# stm32.net
KiCad netlist of a schematic drawn in Altium Designer
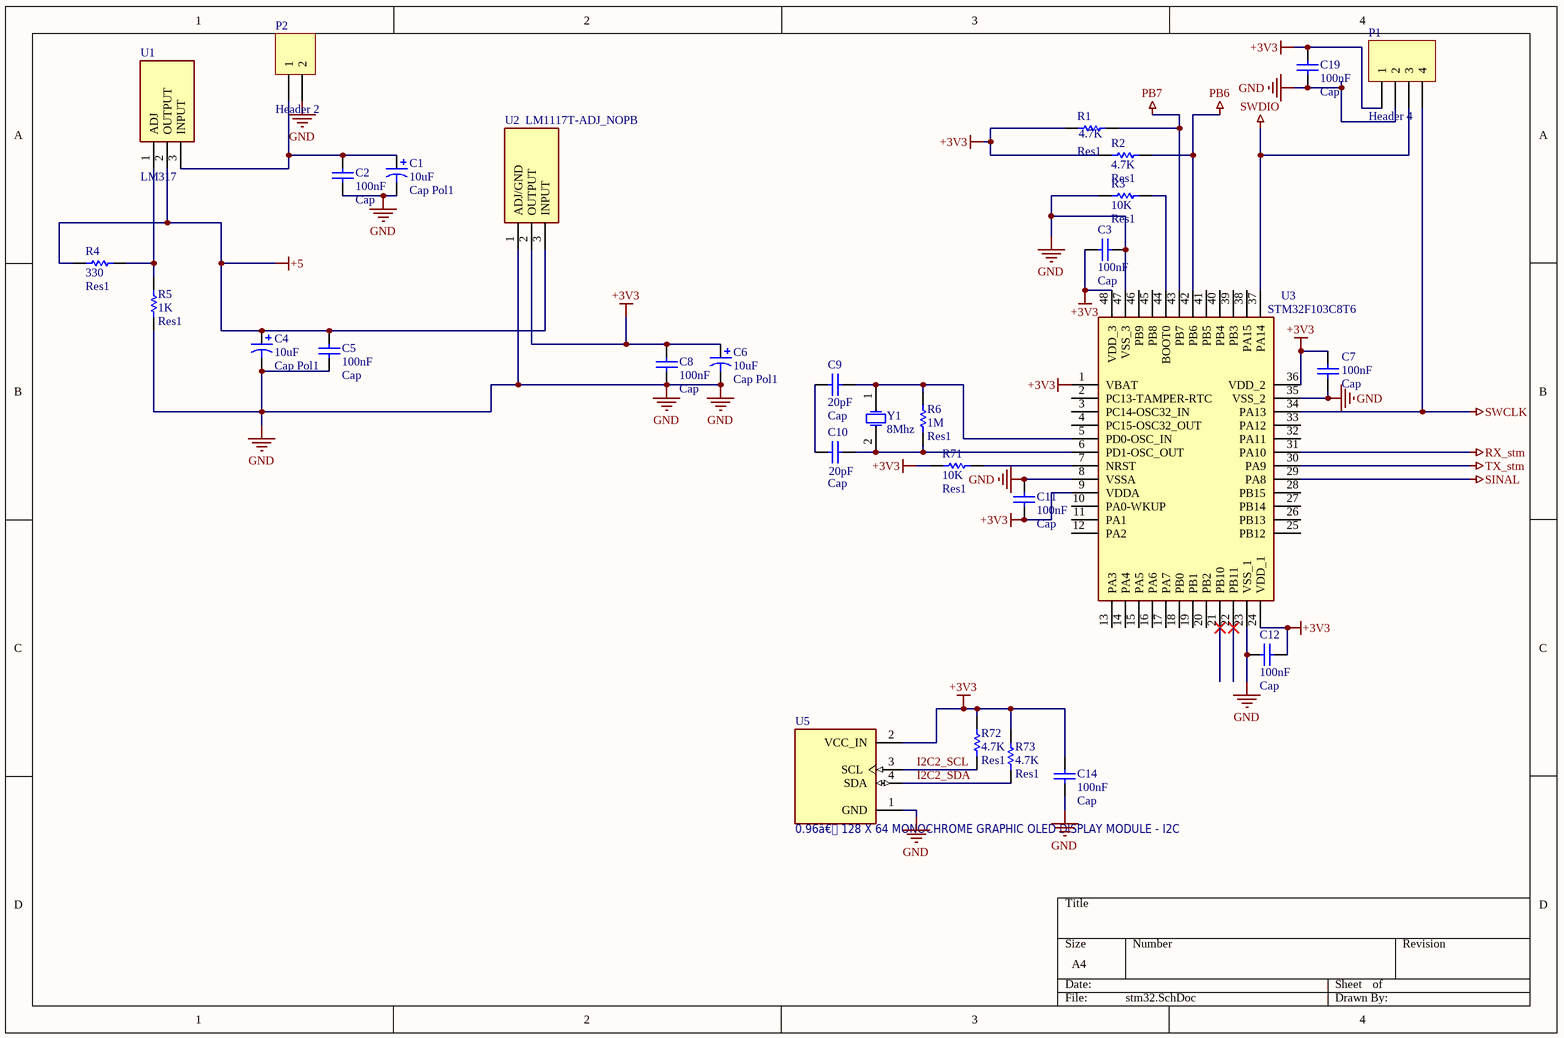
[diagram p0: stm32.SchDoc]

(export (version "E")
  (design (tool "Eeschema 10.0.6"))
  (components
    (comp (ref "C1")
      (value "Cap Pol1")
      (footprint "lib_footprint_projeto:CAP+10uF")
      (description "Polarized Capacitor (Radial)")
      (fields (field (name "ALTIUM_VALUE") "10uF") (field (name "PUBLISHER") "Altium Limited"))
      (libsource (lib "Miscellaneous Devices") (part "Cap Pol1"))
    )
    (comp (ref "C2")
      (value "Cap")
      (footprint "lib_footprint_projeto:CAP100N")
      (description "Capacitor")
      (fields (field (name "ALTIUM_VALUE") "100nF") (field (name "PUBLISHER") "Altium Limited"))
      (libsource (lib "Miscellaneous Devices") (part "Cap"))
    )
    (comp (ref "C3")
      (value "Cap")
      (footprint "lib_footprint_projeto:CAP100N")
      (description "Capacitor")
      (fields (field (name "ALTIUM_VALUE") "100nF") (field (name "PUBLISHER") "Altium Limited"))
      (libsource (lib "Miscellaneous Devices") (part "Cap"))
    )
    (comp (ref "C4")
      (value "Cap Pol1")
      (footprint "lib_footprint_projeto:CAP+10uF")
      (description "Polarized Capacitor (Radial)")
      (fields (field (name "ALTIUM_VALUE") "10uF") (field (name "PUBLISHER") "Altium Limited"))
      (libsource (lib "Miscellaneous Devices") (part "Cap Pol1"))
    )
    (comp (ref "C5")
      (value "Cap")
      (footprint "lib_footprint_projeto:CAP100N")
      (description "Capacitor")
      (fields (field (name "ALTIUM_VALUE") "100nF") (field (name "PUBLISHER") "Altium Limited"))
      (libsource (lib "Miscellaneous Devices") (part "Cap"))
    )
    (comp (ref "C6")
      (value "Cap Pol1")
      (footprint "lib_footprint_projeto:CAP+10uF")
      (description "Polarized Capacitor (Radial)")
      (fields (field (name "ALTIUM_VALUE") "10uF") (field (name "PUBLISHER") "Altium Limited"))
      (libsource (lib "Miscellaneous Devices") (part "Cap Pol1"))
    )
    (comp (ref "C7")
      (value "Cap")
      (footprint "lib_footprint_projeto:CAP100N")
      (description "Capacitor")
      (fields (field (name "ALTIUM_VALUE") "100nF") (field (name "PUBLISHER") "Altium Limited"))
      (libsource (lib "Miscellaneous Devices") (part "Cap"))
    )
    (comp (ref "C8")
      (value "Cap")
      (footprint "lib_footprint_projeto:CAP100N")
      (description "Capacitor")
      (fields (field (name "ALTIUM_VALUE") "100nF") (field (name "PUBLISHER") "Altium Limited"))
      (libsource (lib "Miscellaneous Devices") (part "Cap"))
    )
    (comp (ref "C9")
      (value "Cap")
      (footprint "lib_footprint_projeto:CAP20pF")
      (description "Capacitor")
      (fields (field (name "ALTIUM_VALUE") "20pF") (field (name "PUBLISHER") "Altium Limited"))
      (libsource (lib "Miscellaneous Devices") (part "Cap"))
    )
    (comp (ref "C10")
      (value "Cap")
      (footprint "lib_footprint_projeto:CAP20pF")
      (description "Capacitor")
      (fields (field (name "ALTIUM_VALUE") "20pF") (field (name "PUBLISHER") "Altium Limited"))
      (libsource (lib "Miscellaneous Devices") (part "Cap"))
    )
    (comp (ref "C11")
      (value "Cap")
      (footprint "lib_footprint_projeto:CAP100N")
      (description "Capacitor")
      (fields (field (name "ALTIUM_VALUE") "100nF") (field (name "PUBLISHER") "Altium Limited"))
      (libsource (lib "Miscellaneous Devices") (part "Cap"))
    )
    (comp (ref "C12")
      (value "Cap")
      (footprint "lib_footprint_projeto:CAP100N")
      (description "Capacitor")
      (fields (field (name "ALTIUM_VALUE") "100nF") (field (name "PUBLISHER") "Altium Limited"))
      (libsource (lib "Miscellaneous Devices") (part "Cap"))
    )
    (comp (ref "C14")
      (value "Cap")
      (footprint "lib_footprint_projeto:CAP100N")
      (description "Capacitor")
      (fields (field (name "ALTIUM_VALUE") "100nF") (field (name "PUBLISHER") "Altium Limited"))
      (libsource (lib "Miscellaneous Devices") (part "Cap"))
    )
    (comp (ref "C19")
      (value "Cap")
      (footprint "lib_footprint_projeto:CAP100N")
      (description "Capacitor")
      (fields (field (name "ALTIUM_VALUE") "100nF") (field (name "PUBLISHER") "Altium Limited"))
      (libsource (lib "Miscellaneous Devices") (part "Cap"))
    )
    (comp (ref "P1")
      (value "Header 4")
      (footprint "lib_footprint_projeto:Header 4, 90")
      (description "Header, 4-Pin")
      (fields (field (name "PUBLISHER") "Altium Limited"))
      (libsource (lib "Miscellaneous Connectors") (part "Header 4"))
    )
    (comp (ref "P2")
      (value "Header 2")
      (footprint "lib_footprint_projeto:Terminal block")
      (description "Header, 2-Pin")
      (fields (field (name "PUBLISHER") "Altium Limited"))
      (libsource (lib "Miscellaneous Connectors") (part "Header 2"))
    )
    (comp (ref "R1")
      (value "Res1")
      (footprint "lib_footprint_projeto:RES4.7K")
      (description "Resistor")
      (fields (field (name "ALTIUM_VALUE") "4.7K") (field (name "PUBLISHER") "Altium Limited"))
      (libsource (lib "Miscellaneous Devices") (part "Res1"))
    )
    (comp (ref "R2")
      (value "Res1")
      (footprint "lib_footprint_projeto:RES4.7K")
      (description "Resistor")
      (fields (field (name "ALTIUM_VALUE") "4.7K") (field (name "PUBLISHER") "Altium Limited"))
      (libsource (lib "Miscellaneous Devices") (part "Res1"))
    )
    (comp (ref "R3")
      (value "Res1")
      (footprint "lib_footprint_projeto:RES10K")
      (description "Resistor")
      (fields (field (name "ALTIUM_VALUE") "10K") (field (name "PUBLISHER") "Altium Limited"))
      (libsource (lib "Miscellaneous Devices") (part "Res1"))
    )
    (comp (ref "R4")
      (value "Res1")
      (footprint "lib_footprint_projeto:RES330")
      (description "Resistor")
      (fields (field (name "ALTIUM_VALUE") "330") (field (name "PUBLISHER") "Altium Limited"))
      (libsource (lib "Miscellaneous Devices") (part "Res1"))
    )
    (comp (ref "R5")
      (value "Res1")
      (footprint "lib_footprint_projeto:RES1K")
      (description "Resistor")
      (fields (field (name "ALTIUM_VALUE") "1K") (field (name "PUBLISHER") "Altium Limited"))
      (libsource (lib "Miscellaneous Devices") (part "Res1"))
    )
    (comp (ref "R6")
      (value "Res1")
      (footprint "lib_footprint_projeto:RES1M")
      (description "Resistor")
      (fields (field (name "ALTIUM_VALUE") "1M") (field (name "PUBLISHER") "Altium Limited"))
      (libsource (lib "Miscellaneous Devices") (part "Res1"))
    )
    (comp (ref "R71")
      (value "Res1")
      (footprint "lib_footprint_projeto:RES10K")
      (description "Resistor")
      (fields (field (name "ALTIUM_VALUE") "10K") (field (name "PUBLISHER") "Altium Limited"))
      (libsource (lib "Miscellaneous Devices") (part "Res1"))
    )
    (comp (ref "R72")
      (value "Res1")
      (footprint "lib_footprint_projeto:RES4.7K")
      (description "Resistor")
      (fields (field (name "ALTIUM_VALUE") "4.7K") (field (name "PUBLISHER") "Altium Limited"))
      (libsource (lib "Miscellaneous Devices") (part "Res1"))
    )
    (comp (ref "R73")
      (value "Res1")
      (footprint "lib_footprint_projeto:RES4.7K")
      (description "Resistor")
      (fields (field (name "ALTIUM_VALUE") "4.7K") (field (name "PUBLISHER") "Altium Limited"))
      (libsource (lib "Miscellaneous Devices") (part "Res1"))
    )
    (comp (ref "U1")
      (value "LM317")
      (footprint "LM317")
      (description "TO-220-3L Plastic-Encapsulate Voltage Regulators")
      (libsource (lib "LM317") (part "LM317"))
    )
    (comp (ref "U2")
      (value "LM1117T-ADJ_NOPB")
      (footprint "LM1117T-ADJ_NOPB")
      (description "Space saving 800-mA low-dropout linear regulator with internal current limit")
      (fields
        (field (name "MANUFACTURER_PART_NUMBER") "LM1117T-ADJ/NOPB")
        (field (name "MOUSER PART NUMBER") "926-LM1117T-ADJ/NOPB")
      )
      (libsource (lib "LM1117T-ADJ_NOPB") (part "LM1117T-ADJ_NOPB"))
    )
    (comp (ref "U3")
      (value "STM32F103C8T6")
      (footprint "STM32F103C8T6")
      (description "ARM Cortex-M3 STM32F1 Microcontroller IC 32-Bit Single-Core 72MHz 64KB (64K x 8) FLASH")
      (libsource (lib "STM32F103C8T6") (part "STM32F103C8T6"))
    )
    (comp (ref "U5")
      (value "0.96â€ 128 X 64 MONOCHROME GRAPHIC OLED DISPLAY MODULE - I2C")
      (footprint "lib_footprint_projeto:OLED")
      (fields (field (name "MF") "Display Module") (field (name "MP") "DM-OLED096-636"))
      (libsource (lib "DM-OLED096-636") (part "DM-OLED096-636"))
    )
    (comp (ref "Y1")
      (value "8Mhz")
      (footprint "lib_footprint_projeto:CRISTAL")
      (description "Crystal Oscillator 8Mhz XTAL Crystal, Thru-Hole; 2 Leads; Body 3.1 x 8.2 mm")
      (fields (field (name "PUBLISHER") "Altium Limited"))
      (libsource (lib "Miscellaneous Devices") (part "XTAL"))
    )
  )
  (nets
    (net (code "1") (name "+3V3") (class "Default")
      (node (ref "C11") (pin "1") (pinfunction "1_1") (pintype "passive"))
      (node (ref "C12") (pin "2") (pinfunction "2_2") (pintype "passive"))
      (node (ref "C14") (pin "2") (pinfunction "2_2") (pintype "passive"))
      (node (ref "C19") (pin "1") (pinfunction "1_1") (pintype "passive"))
      (node (ref "C3") (pin "1") (pinfunction "1_1") (pintype "passive"))
      (node (ref "C6") (pin "1") (pinfunction "1_1") (pintype "passive"))
      (node (ref "C7") (pin "2") (pinfunction "2_2") (pintype "passive"))
      (node (ref "C8") (pin "2") (pinfunction "2_2") (pintype "passive"))
      (node (ref "P1") (pin "1") (pinfunction "1_1") (pintype "passive"))
      (node (ref "R1") (pin "1") (pinfunction "1_1") (pintype "passive"))
      (node (ref "R2") (pin "1") (pinfunction "1_1") (pintype "passive"))
      (node (ref "R71") (pin "1") (pinfunction "1_1") (pintype "passive"))
      (node (ref "R72") (pin "2") (pinfunction "2_2") (pintype "passive"))
      (node (ref "R73") (pin "2") (pinfunction "2_2") (pintype "passive"))
      (node (ref "U2") (pin "2") (pinfunction "OUTPUT_2") (pintype "passive"))
      (node (ref "U3") (pin "1") (pinfunction "VBAT_1") (pintype "passive"))
      (node (ref "U3") (pin "24") (pinfunction "VDD_1_24") (pintype "passive"))
      (node (ref "U3") (pin "36") (pinfunction "VDD_2_36") (pintype "passive"))
      (node (ref "U3") (pin "48") (pinfunction "VDD_3_48") (pintype "passive"))
      (node (ref "U3") (pin "9") (pinfunction "VDDA_9") (pintype "passive"))
      (node (ref "U5") (pin "2") (pinfunction "VCC_IN_2") (pintype "power_in"))
    )
    (net (code "2") (name "+5") (class "Default")
      (node (ref "C4") (pin "1") (pinfunction "1_1") (pintype "passive"))
      (node (ref "C5") (pin "2") (pinfunction "2_2") (pintype "passive"))
      (node (ref "R4") (pin "1") (pinfunction "1_1") (pintype "passive"))
      (node (ref "U1") (pin "2") (pinfunction "OUTPUT_2") (pintype "passive"))
      (node (ref "U2") (pin "3") (pinfunction "INPUT_3") (pintype "passive"))
    )
    (net (code "3") (name "/I2C2_SCL") (class "Default")
      (node (ref "R72") (pin "1") (pinfunction "1_1") (pintype "passive"))
      (node (ref "U5") (pin "3") (pinfunction "SCL_3") (pintype "input"))
    )
    (net (code "4") (name "/I2C2_SDA") (class "Default")
      (node (ref "R73") (pin "1") (pinfunction "1_1") (pintype "passive"))
      (node (ref "U5") (pin "4") (pinfunction "SDA_4") (pintype "bidirectional"))
    )
    (net (code "5") (name "GND") (class "Default")
      (node (ref "C1") (pin "2") (pinfunction "2_2") (pintype "passive"))
      (node (ref "C11") (pin "2") (pinfunction "2_2") (pintype "passive"))
      (node (ref "C12") (pin "1") (pinfunction "1_1") (pintype "passive"))
      (node (ref "C14") (pin "1") (pinfunction "1_1") (pintype "passive"))
      (node (ref "C19") (pin "2") (pinfunction "2_2") (pintype "passive"))
      (node (ref "C2") (pin "1") (pinfunction "1_1") (pintype "passive"))
      (node (ref "C3") (pin "2") (pinfunction "2_2") (pintype "passive"))
      (node (ref "C4") (pin "2") (pinfunction "2_2") (pintype "passive"))
      (node (ref "C5") (pin "1") (pinfunction "1_1") (pintype "passive"))
      (node (ref "C6") (pin "2") (pinfunction "2_2") (pintype "passive"))
      (node (ref "C7") (pin "1") (pinfunction "1_1") (pintype "passive"))
      (node (ref "C8") (pin "1") (pinfunction "1_1") (pintype "passive"))
      (node (ref "P1") (pin "2") (pinfunction "2_2") (pintype "passive"))
      (node (ref "P2") (pin "2") (pinfunction "2_2") (pintype "passive"))
      (node (ref "R3") (pin "1") (pinfunction "1_1") (pintype "passive"))
      (node (ref "R5") (pin "1") (pinfunction "1_1") (pintype "passive"))
      (node (ref "U2") (pin "1") (pinfunction "ADJ/GND_1") (pintype "passive"))
      (node (ref "U3") (pin "23") (pinfunction "VSS_1_23") (pintype "passive"))
      (node (ref "U3") (pin "35") (pinfunction "VSS_2_35") (pintype "passive"))
      (node (ref "U3") (pin "47") (pinfunction "VSS_3_47") (pintype "passive"))
      (node (ref "U3") (pin "8") (pinfunction "VSSA_8") (pintype "passive"))
      (node (ref "U5") (pin "1") (pinfunction "GND_1") (pintype "power_in"))
    )
    (net (code "6") (name "Net-(C10-Pad1)") (class "Default")
      (node (ref "C10") (pin "1") (pinfunction "1_1") (pintype "passive"))
      (node (ref "C9") (pin "1") (pinfunction "1_1") (pintype "passive"))
    )
    (net (code "7") (name "Net-(U1-ADJ)") (class "Default")
      (node (ref "R4") (pin "2") (pinfunction "2_2") (pintype "passive"))
      (node (ref "R5") (pin "2") (pinfunction "2_2") (pintype "passive"))
      (node (ref "U1") (pin "1") (pinfunction "ADJ_1") (pintype "passive"))
    )
    (net (code "8") (name "Net-(U1-INPUT)") (class "Default")
      (node (ref "C1") (pin "1") (pinfunction "1_1") (pintype "passive"))
      (node (ref "C2") (pin "2") (pinfunction "2_2") (pintype "passive"))
      (node (ref "P2") (pin "1") (pinfunction "1_1") (pintype "passive"))
      (node (ref "U1") (pin "3") (pinfunction "INPUT_3") (pintype "passive"))
    )
    (net (code "9") (name "Net-(U3-BOOT0)") (class "Default")
      (node (ref "R3") (pin "2") (pinfunction "2_2") (pintype "passive"))
      (node (ref "U3") (pin "44") (pinfunction "BOOT0_44") (pintype "passive"))
    )
    (net (code "10") (name "Net-(U3-NRST)") (class "Default")
      (node (ref "R71") (pin "2") (pinfunction "2_2") (pintype "passive"))
      (node (ref "U3") (pin "7") (pinfunction "NRST_7") (pintype "passive"))
    )
    (net (code "11") (name "Net-(U3-PD0-OSC_IN)") (class "Default")
      (node (ref "C9") (pin "2") (pinfunction "2_2") (pintype "passive"))
      (node (ref "R6") (pin "2") (pinfunction "2_2") (pintype "passive"))
      (node (ref "U3") (pin "5") (pinfunction "PD0-OSC_IN_5") (pintype "passive"))
      (node (ref "Y1") (pin "1") (pinfunction "OSC1_1") (pintype "passive"))
    )
    (net (code "12") (name "Net-(U3-PD1-OSC_OUT)") (class "Default")
      (node (ref "C10") (pin "2") (pinfunction "2_2") (pintype "passive"))
      (node (ref "R6") (pin "1") (pinfunction "1_1") (pintype "passive"))
      (node (ref "U3") (pin "6") (pinfunction "PD1-OSC_OUT_6") (pintype "passive"))
      (node (ref "Y1") (pin "2") (pinfunction "OSC2_2") (pintype "passive"))
    )
    (net (code "13") (name "PB6") (class "Default")
      (node (ref "R2") (pin "2") (pinfunction "2_2") (pintype "passive"))
      (node (ref "U3") (pin "42") (pinfunction "PB6_42") (pintype "passive"))
    )
    (net (code "14") (name "PB7") (class "Default")
      (node (ref "R1") (pin "2") (pinfunction "2_2") (pintype "passive"))
      (node (ref "U3") (pin "43") (pinfunction "PB7_43") (pintype "passive"))
    )
    (net (code "15") (name "RX_stm") (class "Default")
      (node (ref "U3") (pin "31") (pinfunction "PA10_31") (pintype "passive"))
    )
    (net (code "16") (name "SINAL") (class "Default")
      (node (ref "U3") (pin "29") (pinfunction "PA8_29") (pintype "passive"))
    )
    (net (code "17") (name "SWCLK") (class "Default")
      (node (ref "P1") (pin "4") (pinfunction "4_4") (pintype "passive"))
      (node (ref "U3") (pin "34") (pinfunction "PA13_34") (pintype "passive"))
    )
    (net (code "18") (name "SWDIO") (class "Default")
      (node (ref "P1") (pin "3") (pinfunction "3_3") (pintype "passive"))
      (node (ref "U3") (pin "37") (pinfunction "PA14_37") (pintype "passive"))
    )
    (net (code "19") (name "TX_stm") (class "Default")
      (node (ref "U3") (pin "30") (pinfunction "PA9_30") (pintype "passive"))
    )
    (net (code "20") (name "unconnected-(U3-PA0-WKUP-Pad10)") (class "Default")
      (node (ref "U3") (pin "10") (pinfunction "PA0-WKUP_10") (pintype "passive"))
    )
    (net (code "21") (name "unconnected-(U3-PA1-Pad11)") (class "Default")
      (node (ref "U3") (pin "11") (pinfunction "PA1_11") (pintype "passive"))
    )
    (net (code "22") (name "unconnected-(U3-PA2-Pad12)") (class "Default")
      (node (ref "U3") (pin "12") (pinfunction "PA2_12") (pintype "passive"))
    )
    (net (code "23") (name "unconnected-(U3-PA3-Pad13)") (class "Default")
      (node (ref "U3") (pin "13") (pinfunction "PA3_13") (pintype "passive"))
    )
    (net (code "24") (name "unconnected-(U3-PA4-Pad14)") (class "Default")
      (node (ref "U3") (pin "14") (pinfunction "PA4_14") (pintype "passive"))
    )
    (net (code "25") (name "unconnected-(U3-PA5-Pad15)") (class "Default")
      (node (ref "U3") (pin "15") (pinfunction "PA5_15") (pintype "passive"))
    )
    (net (code "26") (name "unconnected-(U3-PA6-Pad16)") (class "Default")
      (node (ref "U3") (pin "16") (pinfunction "PA6_16") (pintype "passive"))
    )
    (net (code "27") (name "unconnected-(U3-PA7-Pad17)") (class "Default")
      (node (ref "U3") (pin "17") (pinfunction "PA7_17") (pintype "passive"))
    )
    (net (code "28") (name "unconnected-(U3-PA11-Pad32)") (class "Default")
      (node (ref "U3") (pin "32") (pinfunction "PA11_32") (pintype "passive"))
    )
    (net (code "29") (name "unconnected-(U3-PA12-Pad33)") (class "Default")
      (node (ref "U3") (pin "33") (pinfunction "PA12_33") (pintype "passive"))
    )
    (net (code "30") (name "unconnected-(U3-PA15-Pad38)") (class "Default")
      (node (ref "U3") (pin "38") (pinfunction "PA15_38") (pintype "passive"))
    )
    (net (code "31") (name "unconnected-(U3-PB0-Pad18)") (class "Default")
      (node (ref "U3") (pin "18") (pinfunction "PB0_18") (pintype "passive"))
    )
    (net (code "32") (name "unconnected-(U3-PB1-Pad19)") (class "Default")
      (node (ref "U3") (pin "19") (pinfunction "PB1_19") (pintype "passive"))
    )
    (net (code "33") (name "unconnected-(U3-PB2-Pad20)") (class "Default")
      (node (ref "U3") (pin "20") (pinfunction "PB2_20") (pintype "passive"))
    )
    (net (code "34") (name "unconnected-(U3-PB3-Pad39)") (class "Default")
      (node (ref "U3") (pin "39") (pinfunction "PB3_39") (pintype "passive"))
    )
    (net (code "35") (name "unconnected-(U3-PB4-Pad40)") (class "Default")
      (node (ref "U3") (pin "40") (pinfunction "PB4_40") (pintype "passive"))
    )
    (net (code "36") (name "unconnected-(U3-PB5-Pad41)") (class "Default")
      (node (ref "U3") (pin "41") (pinfunction "PB5_41") (pintype "passive"))
    )
    (net (code "37") (name "unconnected-(U3-PB8-Pad45)") (class "Default")
      (node (ref "U3") (pin "45") (pinfunction "PB8_45") (pintype "passive"))
    )
    (net (code "38") (name "unconnected-(U3-PB9-Pad46)") (class "Default")
      (node (ref "U3") (pin "46") (pinfunction "PB9_46") (pintype "passive"))
    )
    (net (code "39") (name "unconnected-(U3-PB10-Pad21)") (class "Default")
      (node (ref "U3") (pin "21") (pinfunction "PB10_21") (pintype "passive+no_connect"))
    )
    (net (code "40") (name "unconnected-(U3-PB11-Pad22)") (class "Default")
      (node (ref "U3") (pin "22") (pinfunction "PB11_22") (pintype "passive+no_connect"))
    )
    (net (code "41") (name "unconnected-(U3-PB12-Pad25)") (class "Default")
      (node (ref "U3") (pin "25") (pinfunction "PB12_25") (pintype "passive"))
    )
    (net (code "42") (name "unconnected-(U3-PB13-Pad26)") (class "Default")
      (node (ref "U3") (pin "26") (pinfunction "PB13_26") (pintype "passive"))
    )
    (net (code "43") (name "unconnected-(U3-PB14-Pad27)") (class "Default")
      (node (ref "U3") (pin "27") (pinfunction "PB14_27") (pintype "passive"))
    )
    (net (code "44") (name "unconnected-(U3-PB15-Pad28)") (class "Default")
      (node (ref "U3") (pin "28") (pinfunction "PB15_28") (pintype "passive"))
    )
    (net (code "45") (name "unconnected-(U3-PC13-TAMPER-RTC-Pad2)") (class "Default")
      (node (ref "U3") (pin "2") (pinfunction "PC13-TAMPER-RTC_2") (pintype "passive"))
    )
    (net (code "46") (name "unconnected-(U3-PC14-OSC32_IN-Pad3)") (class "Default")
      (node (ref "U3") (pin "3") (pinfunction "PC14-OSC32_IN_3") (pintype "passive"))
    )
    (net (code "47") (name "unconnected-(U3-PC15-OSC32_OUT-Pad4)") (class "Default")
      (node (ref "U3") (pin "4") (pinfunction "PC15-OSC32_OUT_4") (pintype "passive"))
    )
  )
)
